# A_slave_stm32.net
KiCad netlist of a schematic drawn in EAGLE
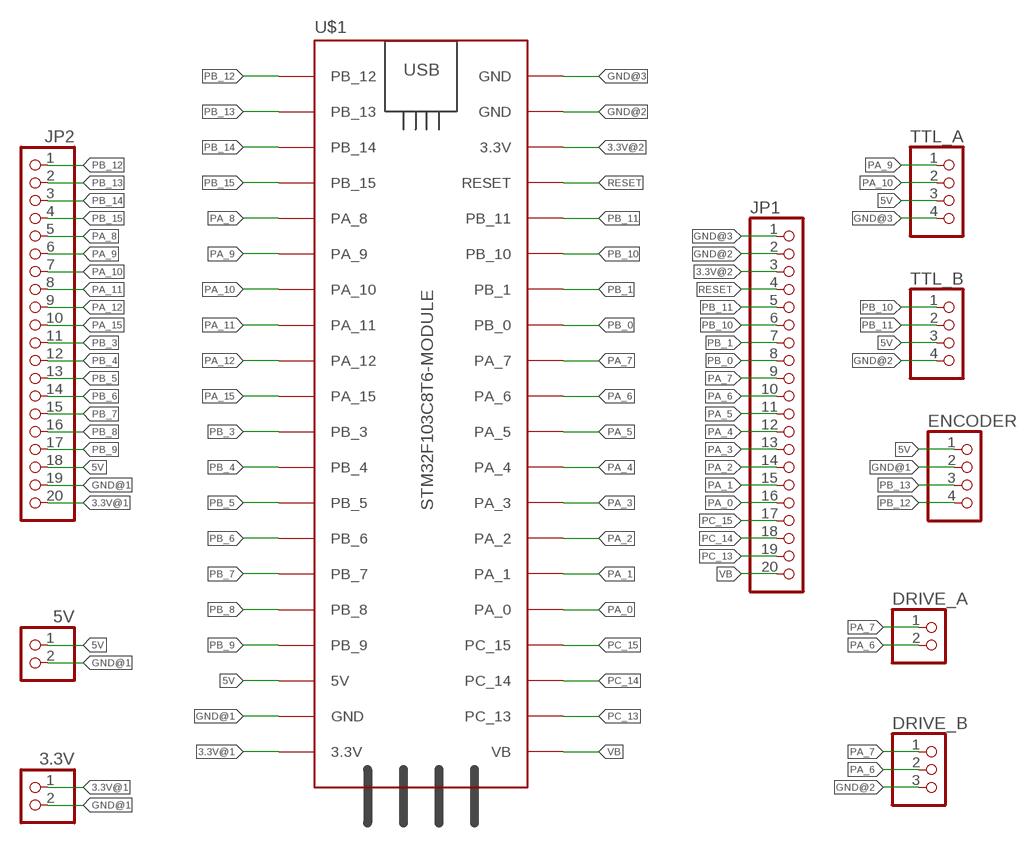
[diagram p0: schematic, sheet 1]

(export (version "E")
  (design (tool "Eeschema 10.0.6"))
  (components
    (comp (ref "3.3V")
      (value "PINHD-2_DATA")
      (footprint "eagle-import:1X02_DATA")
      (libsource (lib "eagle-import") (part "PINHD-2_DATA"))
    )
    (comp (ref "5V")
      (value "PINHD-2_DATA")
      (footprint "eagle-import:1X02_DATA")
      (libsource (lib "eagle-import") (part "PINHD-2_DATA"))
    )
    (comp (ref "DRIVE_A")
      (value "PINHD-2_DATA")
      (footprint "eagle-import:1X02_DATA")
      (libsource (lib "eagle-import") (part "PINHD-2_DATA"))
    )
    (comp (ref "DRIVE_B")
      (value "PINHD-3_DATA")
      (footprint "eagle-import:1X03_DATA")
      (libsource (lib "eagle-import") (part "PINHD-3_DATA"))
    )
    (comp (ref "ENCODER")
      (value "PINHD-4_DATA")
      (footprint "eagle-import:1X04_DATA")
      (libsource (lib "eagle-import") (part "PINHD-4_DATA"))
    )
    (comp (ref "JP1")
      (value "PINHD-1X20")
      (footprint "eagle-import:1X20")
      (libsource (lib "eagle-import") (part "PINHD-1X20"))
    )
    (comp (ref "JP2")
      (value "PINHD-1X20")
      (footprint "eagle-import:1X20")
      (libsource (lib "eagle-import") (part "PINHD-1X20"))
    )
    (comp (ref "TTL_A")
      (value "PINHD-4_DATA")
      (footprint "eagle-import:1X04_DATA")
      (libsource (lib "eagle-import") (part "PINHD-4_DATA"))
    )
    (comp (ref "TTL_B")
      (value "PINHD-4_DATA")
      (footprint "eagle-import:1X04_DATA")
      (libsource (lib "eagle-import") (part "PINHD-4_DATA"))
    )
    (comp (ref "U$1")
      (value "STM32F103C8T6-MODULE")
      (footprint "eagle-import:STM32F103C8T6-MODULE")
      (libsource (lib "eagle-import") (part "STM32F103C8T6-MODULE"))
    )
  )
  (nets
    (net (code "1") (name "3.3V@1") (class "Default")
      (node (ref "3.3V") (pin "1") (pinfunction "1_1") (pintype "passive"))
      (node (ref "JP2") (pin "20") (pinfunction "20_20") (pintype "passive"))
      (node (ref "U$1") (pin "3.3V_1") (pinfunction "3.3V_3.3V_1") (pintype "bidirectional"))
    )
    (net (code "2") (name "3.3V@2") (class "Default")
      (node (ref "JP1") (pin "3") (pinfunction "3_3") (pintype "passive"))
      (node (ref "U$1") (pin "3.3V_2") (pinfunction "3.3V_3.3V_2") (pintype "bidirectional"))
    )
    (net (code "3") (name "5V") (class "Default")
      (node (ref "5V") (pin "1") (pinfunction "1_1") (pintype "passive"))
      (node (ref "ENCODER") (pin "1") (pinfunction "1_1") (pintype "passive"))
      (node (ref "JP2") (pin "18") (pinfunction "18_18") (pintype "passive"))
      (node (ref "TTL_A") (pin "3") (pinfunction "3_3") (pintype "passive"))
      (node (ref "TTL_B") (pin "3") (pinfunction "3_3") (pintype "passive"))
      (node (ref "U$1") (pin "5V") (pinfunction "5V_5V") (pintype "bidirectional"))
    )
    (net (code "4") (name "GND@1") (class "Default")
      (node (ref "3.3V") (pin "2") (pinfunction "2_2") (pintype "passive"))
      (node (ref "5V") (pin "2") (pinfunction "2_2") (pintype "passive"))
      (node (ref "ENCODER") (pin "2") (pinfunction "2_2") (pintype "passive"))
      (node (ref "JP2") (pin "19") (pinfunction "19_19") (pintype "passive"))
      (node (ref "U$1") (pin "GND_1") (pinfunction "GND_GND_1") (pintype "bidirectional"))
    )
    (net (code "5") (name "GND@2") (class "Default")
      (node (ref "DRIVE_B") (pin "3") (pinfunction "3_3") (pintype "passive"))
      (node (ref "JP1") (pin "2") (pinfunction "2_2") (pintype "passive"))
      (node (ref "TTL_B") (pin "4") (pinfunction "4_4") (pintype "passive"))
      (node (ref "U$1") (pin "GND_2") (pinfunction "GND_GND_2") (pintype "bidirectional"))
    )
    (net (code "6") (name "GND@3") (class "Default")
      (node (ref "JP1") (pin "1") (pinfunction "1_1") (pintype "passive"))
      (node (ref "TTL_A") (pin "4") (pinfunction "4_4") (pintype "passive"))
      (node (ref "U$1") (pin "GND_3") (pinfunction "GND_GND_3") (pintype "power_in"))
    )
    (net (code "7") (name "PA_0") (class "Default")
      (node (ref "JP1") (pin "16") (pinfunction "16_16") (pintype "passive"))
      (node (ref "U$1") (pin "PA_0") (pinfunction "PA_0_PA_0") (pintype "bidirectional"))
    )
    (net (code "8") (name "PA_1") (class "Default")
      (node (ref "JP1") (pin "15") (pinfunction "15_15") (pintype "passive"))
      (node (ref "U$1") (pin "PA_1") (pinfunction "PA_1_PA_1") (pintype "bidirectional"))
    )
    (net (code "9") (name "PA_2") (class "Default")
      (node (ref "JP1") (pin "14") (pinfunction "14_14") (pintype "passive"))
      (node (ref "U$1") (pin "PA_2") (pinfunction "PA_2_PA_2") (pintype "bidirectional"))
    )
    (net (code "10") (name "PA_3") (class "Default")
      (node (ref "JP1") (pin "13") (pinfunction "13_13") (pintype "passive"))
      (node (ref "U$1") (pin "PA_3") (pinfunction "PA_3_PA_3") (pintype "bidirectional"))
    )
    (net (code "11") (name "PA_4") (class "Default")
      (node (ref "JP1") (pin "12") (pinfunction "12_12") (pintype "passive"))
      (node (ref "U$1") (pin "PA_4") (pinfunction "PA_4_PA_4") (pintype "bidirectional"))
    )
    (net (code "12") (name "PA_5") (class "Default")
      (node (ref "JP1") (pin "11") (pinfunction "11_11") (pintype "passive"))
      (node (ref "U$1") (pin "PA_5") (pinfunction "PA_5_PA_5") (pintype "bidirectional"))
    )
    (net (code "13") (name "PA_6") (class "Default")
      (node (ref "DRIVE_A") (pin "2") (pinfunction "2_2") (pintype "passive"))
      (node (ref "DRIVE_B") (pin "2") (pinfunction "2_2") (pintype "passive"))
      (node (ref "JP1") (pin "10") (pinfunction "10_10") (pintype "passive"))
      (node (ref "U$1") (pin "PA_6") (pinfunction "PA_6_PA_6") (pintype "bidirectional"))
    )
    (net (code "14") (name "PA_7") (class "Default")
      (node (ref "DRIVE_A") (pin "1") (pinfunction "1_1") (pintype "passive"))
      (node (ref "DRIVE_B") (pin "1") (pinfunction "1_1") (pintype "passive"))
      (node (ref "JP1") (pin "9") (pinfunction "9_9") (pintype "passive"))
      (node (ref "U$1") (pin "PA_7") (pinfunction "PA_7_PA_7") (pintype "bidirectional"))
    )
    (net (code "15") (name "PA_8") (class "Default")
      (node (ref "JP2") (pin "5") (pinfunction "5_5") (pintype "passive"))
      (node (ref "U$1") (pin "PA_8") (pinfunction "PA_8_PA_8") (pintype "bidirectional"))
    )
    (net (code "16") (name "PA_9") (class "Default")
      (node (ref "JP2") (pin "6") (pinfunction "6_6") (pintype "passive"))
      (node (ref "TTL_A") (pin "1") (pinfunction "1_1") (pintype "passive"))
      (node (ref "U$1") (pin "PA_9") (pinfunction "PA_9_PA_9") (pintype "bidirectional"))
    )
    (net (code "17") (name "PA_10") (class "Default")
      (node (ref "JP2") (pin "7") (pinfunction "7_7") (pintype "passive"))
      (node (ref "TTL_A") (pin "2") (pinfunction "2_2") (pintype "passive"))
      (node (ref "U$1") (pin "PA_10") (pinfunction "PA_10_PA_10") (pintype "bidirectional"))
    )
    (net (code "18") (name "PA_11") (class "Default")
      (node (ref "JP2") (pin "8") (pinfunction "8_8") (pintype "passive"))
      (node (ref "U$1") (pin "PA_11") (pinfunction "PA_11_PA_11") (pintype "bidirectional"))
    )
    (net (code "19") (name "PA_12") (class "Default")
      (node (ref "JP2") (pin "9") (pinfunction "9_9") (pintype "passive"))
      (node (ref "U$1") (pin "PA_12") (pinfunction "PA_12_PA_12") (pintype "bidirectional"))
    )
    (net (code "20") (name "PA_15") (class "Default")
      (node (ref "JP2") (pin "10") (pinfunction "10_10") (pintype "passive"))
      (node (ref "U$1") (pin "PA_15") (pinfunction "PA_15_PA_15") (pintype "bidirectional"))
    )
    (net (code "21") (name "PB_0") (class "Default")
      (node (ref "JP1") (pin "8") (pinfunction "8_8") (pintype "passive"))
      (node (ref "U$1") (pin "PB_0") (pinfunction "PB_0_PB_0") (pintype "bidirectional"))
    )
    (net (code "22") (name "PB_1") (class "Default")
      (node (ref "JP1") (pin "7") (pinfunction "7_7") (pintype "passive"))
      (node (ref "U$1") (pin "PB_1") (pinfunction "PB_1_PB_1") (pintype "bidirectional"))
    )
    (net (code "23") (name "PB_3") (class "Default")
      (node (ref "JP2") (pin "11") (pinfunction "11_11") (pintype "passive"))
      (node (ref "U$1") (pin "PB_3") (pinfunction "PB_3_PB_3") (pintype "bidirectional"))
    )
    (net (code "24") (name "PB_4") (class "Default")
      (node (ref "JP2") (pin "12") (pinfunction "12_12") (pintype "passive"))
      (node (ref "U$1") (pin "PB_4") (pinfunction "PB_4_PB_4") (pintype "bidirectional"))
    )
    (net (code "25") (name "PB_5") (class "Default")
      (node (ref "JP2") (pin "13") (pinfunction "13_13") (pintype "passive"))
      (node (ref "U$1") (pin "PB_5") (pinfunction "PB_5_PB_5") (pintype "bidirectional"))
    )
    (net (code "26") (name "PB_6") (class "Default")
      (node (ref "JP2") (pin "14") (pinfunction "14_14") (pintype "passive"))
      (node (ref "U$1") (pin "PB_6") (pinfunction "PB_6_PB_6") (pintype "bidirectional"))
    )
    (net (code "27") (name "PB_7") (class "Default")
      (node (ref "JP2") (pin "15") (pinfunction "15_15") (pintype "passive"))
      (node (ref "U$1") (pin "PB_7") (pinfunction "PB_7_PB_7") (pintype "bidirectional"))
    )
    (net (code "28") (name "PB_8") (class "Default")
      (node (ref "JP2") (pin "16") (pinfunction "16_16") (pintype "passive"))
      (node (ref "U$1") (pin "PB_8") (pinfunction "PB_8_PB_8") (pintype "bidirectional"))
    )
    (net (code "29") (name "PB_9") (class "Default")
      (node (ref "JP2") (pin "17") (pinfunction "17_17") (pintype "passive"))
      (node (ref "U$1") (pin "PB_9") (pinfunction "PB_9_PB_9") (pintype "bidirectional"))
    )
    (net (code "30") (name "PB_10") (class "Default")
      (node (ref "JP1") (pin "6") (pinfunction "6_6") (pintype "passive"))
      (node (ref "TTL_B") (pin "1") (pinfunction "1_1") (pintype "passive"))
      (node (ref "U$1") (pin "PB_10") (pinfunction "PB_10_PB_10") (pintype "bidirectional"))
    )
    (net (code "31") (name "PB_11") (class "Default")
      (node (ref "JP1") (pin "5") (pinfunction "5_5") (pintype "passive"))
      (node (ref "TTL_B") (pin "2") (pinfunction "2_2") (pintype "passive"))
      (node (ref "U$1") (pin "PB_11") (pinfunction "PB_11_PB_11") (pintype "bidirectional"))
    )
    (net (code "32") (name "PB_12") (class "Default")
      (node (ref "ENCODER") (pin "4") (pinfunction "4_4") (pintype "passive"))
      (node (ref "JP2") (pin "1") (pinfunction "1_1") (pintype "passive"))
      (node (ref "U$1") (pin "PB_12") (pinfunction "PB_12_PB_12") (pintype "bidirectional"))
    )
    (net (code "33") (name "PB_13") (class "Default")
      (node (ref "ENCODER") (pin "3") (pinfunction "3_3") (pintype "passive"))
      (node (ref "JP2") (pin "2") (pinfunction "2_2") (pintype "passive"))
      (node (ref "U$1") (pin "PB_13") (pinfunction "PB_13_PB_13") (pintype "bidirectional"))
    )
    (net (code "34") (name "PB_14") (class "Default")
      (node (ref "JP2") (pin "3") (pinfunction "3_3") (pintype "passive"))
      (node (ref "U$1") (pin "PB_14") (pinfunction "PB_14_PB_14") (pintype "bidirectional"))
    )
    (net (code "35") (name "PB_15") (class "Default")
      (node (ref "JP2") (pin "4") (pinfunction "4_4") (pintype "passive"))
      (node (ref "U$1") (pin "PB_15") (pinfunction "PB_15_PB_15") (pintype "bidirectional"))
    )
    (net (code "36") (name "PC_13") (class "Default")
      (node (ref "JP1") (pin "19") (pinfunction "19_19") (pintype "passive"))
      (node (ref "U$1") (pin "PC_13") (pinfunction "PC_13_PC_13") (pintype "bidirectional"))
    )
    (net (code "37") (name "PC_14") (class "Default")
      (node (ref "JP1") (pin "18") (pinfunction "18_18") (pintype "passive"))
      (node (ref "U$1") (pin "PC_14") (pinfunction "PC_14_PC_14") (pintype "bidirectional"))
    )
    (net (code "38") (name "PC_15") (class "Default")
      (node (ref "JP1") (pin "17") (pinfunction "17_17") (pintype "passive"))
      (node (ref "U$1") (pin "PC_15") (pinfunction "PC_15_PC_15") (pintype "bidirectional"))
    )
    (net (code "39") (name "RESET") (class "Default")
      (node (ref "JP1") (pin "4") (pinfunction "4_4") (pintype "passive"))
      (node (ref "U$1") (pin "RESET") (pinfunction "RESET_RESET") (pintype "bidirectional"))
    )
    (net (code "40") (name "VB") (class "Default")
      (node (ref "JP1") (pin "20") (pinfunction "20_20") (pintype "passive"))
      (node (ref "U$1") (pin "VB") (pinfunction "VB_VB") (pintype "bidirectional"))
    )
  )
)
